# RADG-Connector-S04-V00.net
KiCad netlist of a schematic drawn in Altium Designer
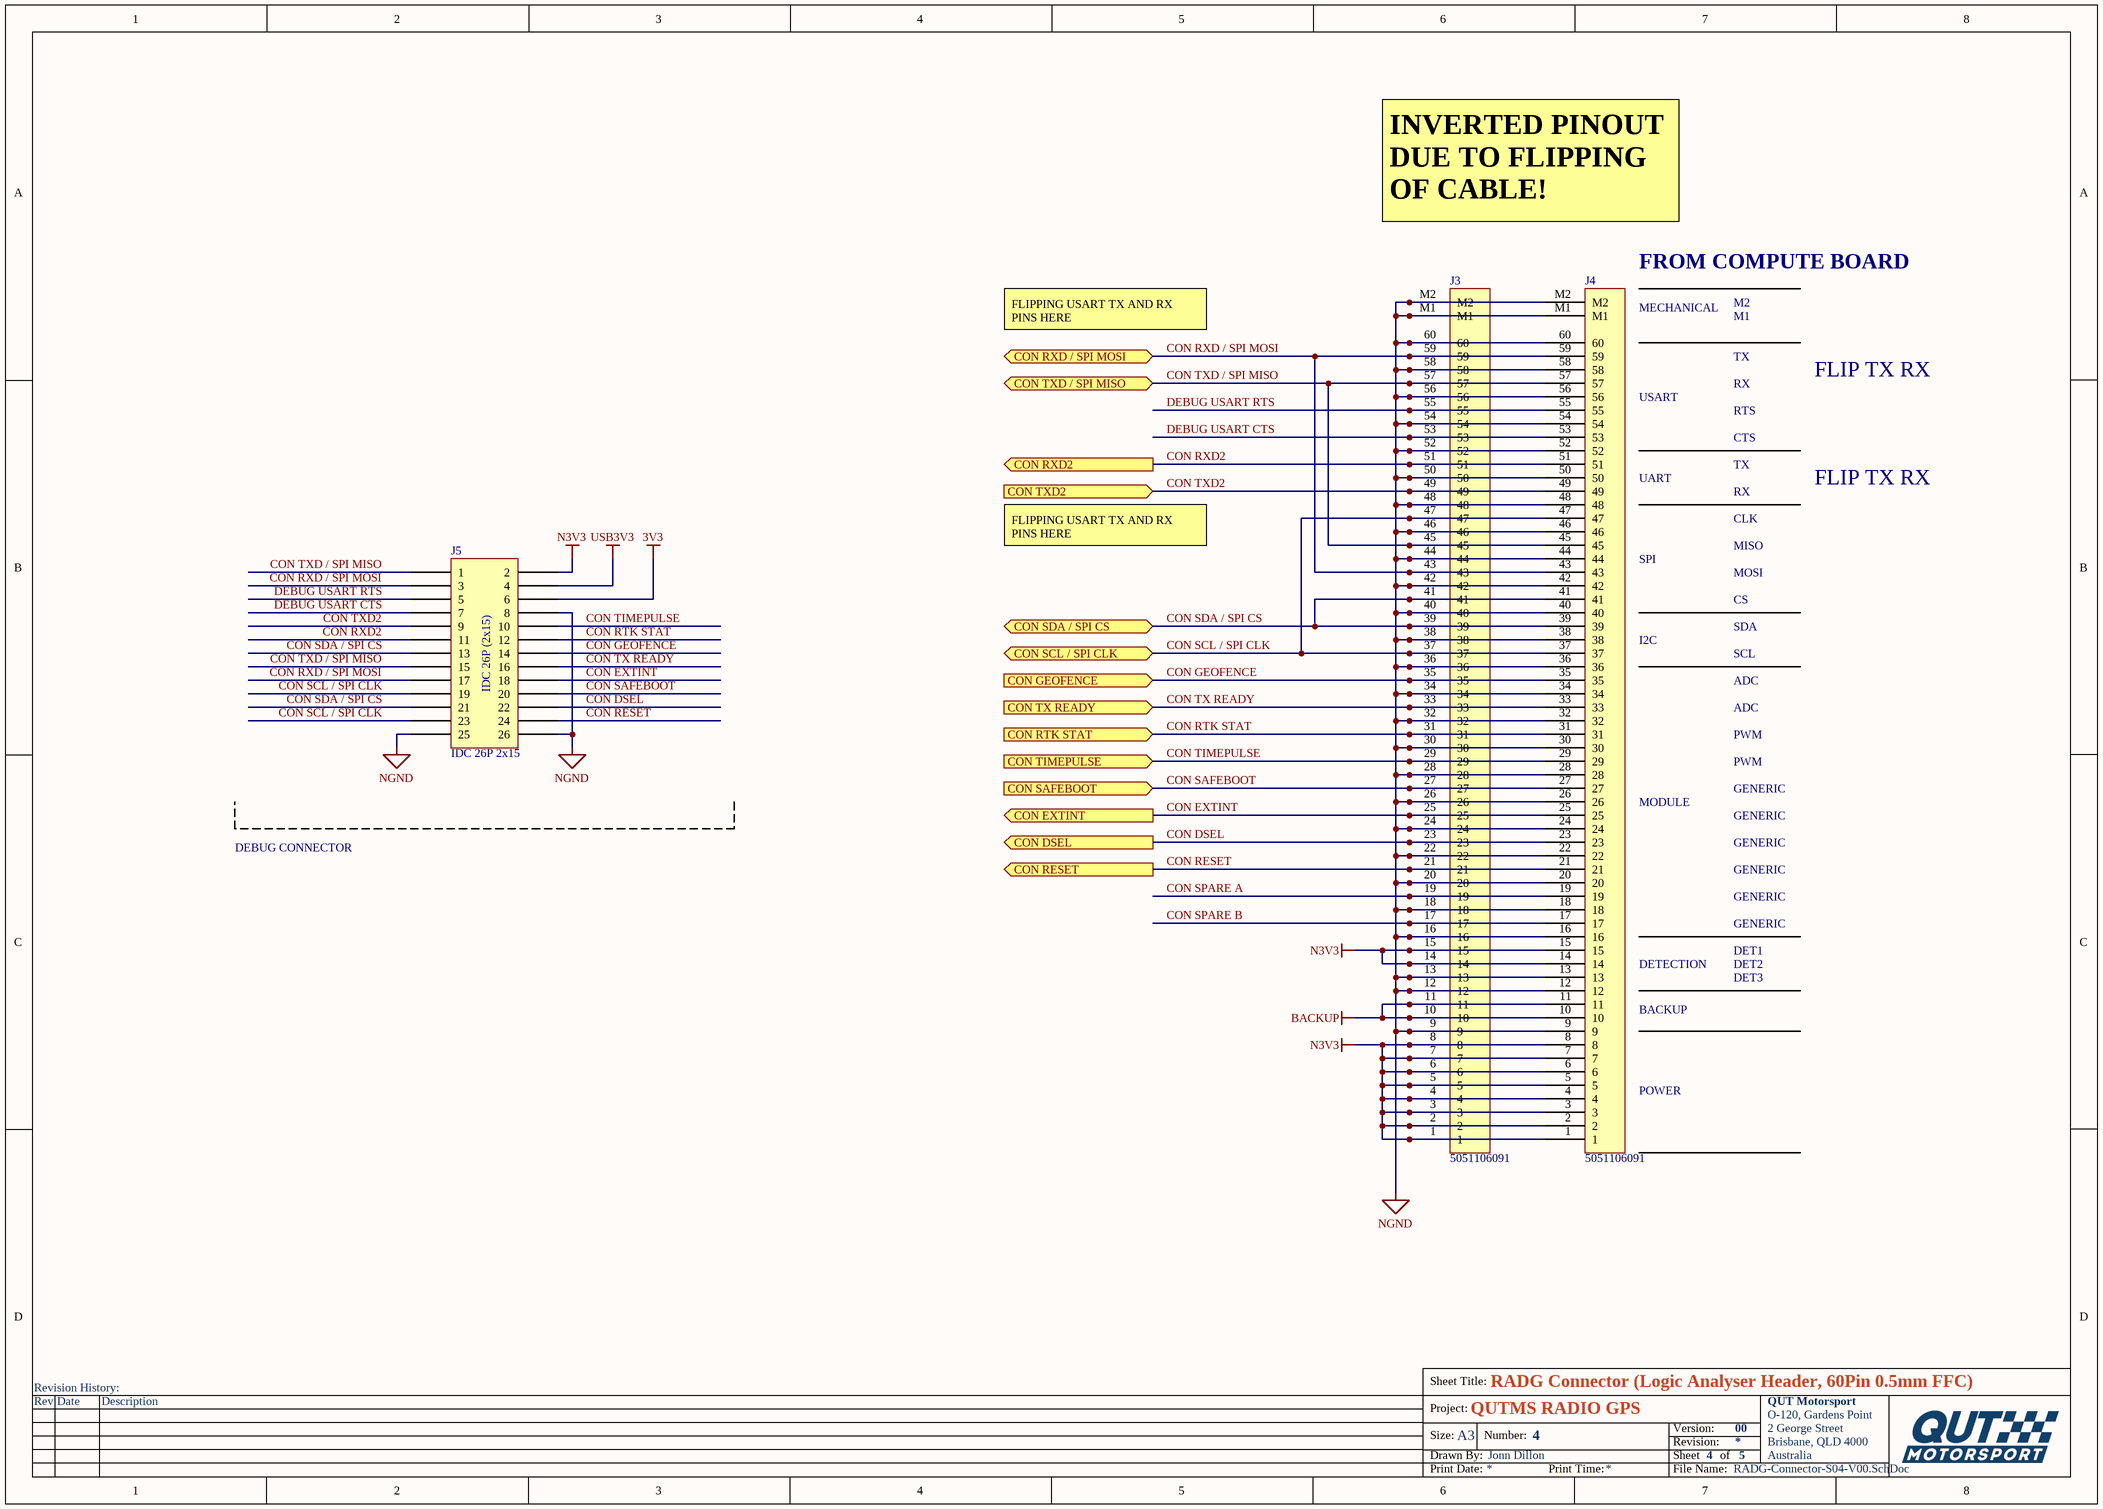
[diagram p0: RADG-Connector-S04-V00.SchDoc]

(export (version "E")
  (design (tool "Eeschema 10.0.6"))
  (components
    (comp (ref "J3")
      (value "5051106091")
      (footprint "5051106091")
      (description "60 Position FFC, FPC Connector Contacts, Bottom 0.020\" (0.50mm) Surface Mount, Right Angle")
      (libsource (lib "QUTMS_FFCConnectors") (part "5051106091"))
    )
    (comp (ref "J4")
      (value "5051106091")
      (footprint "5051106091")
      (description "60 Position FFC, FPC Connector Contacts, Bottom 0.020\" (0.50mm) Surface Mount, Right Angle")
      (libsource (lib "QUTMS_FFCConnectors") (part "5051106091"))
    )
    (comp (ref "J5")
      (value "IDC 26P 2x15")
      (footprint "IDC 2.54mm EDGE MOUNT 26p")
      (libsource (lib "QUTMS_IDCConnectors") (part "IDC 26P 2x13"))
    )
  )
  (nets
    (net (code "1") (name "/CON DSEL") (class "Default")
      (node (ref "J3") (pin "23") (pinfunction "23_23") (pintype "passive"))
      (node (ref "J4") (pin "23") (pinfunction "23_23") (pintype "passive"))
      (node (ref "J5") (pin "22") (pinfunction "22_22") (pintype "passive"))
    )
    (net (code "2") (name "/CON EXTINT") (class "Default")
      (node (ref "J3") (pin "25") (pinfunction "25_25") (pintype "passive"))
      (node (ref "J4") (pin "25") (pinfunction "25_25") (pintype "passive"))
      (node (ref "J5") (pin "18") (pinfunction "18_18") (pintype "passive"))
    )
    (net (code "3") (name "/CON GEOFENCE") (class "Default")
      (node (ref "J3") (pin "35") (pinfunction "35_35") (pintype "passive"))
      (node (ref "J4") (pin "35") (pinfunction "35_35") (pintype "passive"))
      (node (ref "J5") (pin "14") (pinfunction "14_14") (pintype "passive"))
    )
    (net (code "4") (name "/CON RESET") (class "Default")
      (node (ref "J3") (pin "21") (pinfunction "21_21") (pintype "passive"))
      (node (ref "J4") (pin "21") (pinfunction "21_21") (pintype "passive"))
      (node (ref "J5") (pin "24") (pinfunction "24_24") (pintype "passive"))
    )
    (net (code "5") (name "/CON RTK STAT") (class "Default")
      (node (ref "J3") (pin "31") (pinfunction "31_31") (pintype "passive"))
      (node (ref "J4") (pin "31") (pinfunction "31_31") (pintype "passive"))
      (node (ref "J5") (pin "12") (pinfunction "12_12") (pintype "passive"))
    )
    (net (code "6") (name "/CON RXD {slash} SPI MOSI") (class "Default")
      (node (ref "J3") (pin "43") (pinfunction "43_43") (pintype "passive"))
      (node (ref "J3") (pin "59") (pinfunction "59_59") (pintype "passive"))
      (node (ref "J4") (pin "43") (pinfunction "43_43") (pintype "passive"))
      (node (ref "J4") (pin "59") (pinfunction "59_59") (pintype "passive"))
      (node (ref "J5") (pin "17") (pinfunction "17_17") (pintype "passive"))
      (node (ref "J5") (pin "3") (pinfunction "3_3") (pintype "passive"))
    )
    (net (code "7") (name "/CON RXD2") (class "Default")
      (node (ref "J3") (pin "51") (pinfunction "51_51") (pintype "passive"))
      (node (ref "J4") (pin "51") (pinfunction "51_51") (pintype "passive"))
      (node (ref "J5") (pin "11") (pinfunction "11_11") (pintype "passive"))
    )
    (net (code "8") (name "/CON SAFEBOOT") (class "Default")
      (node (ref "J3") (pin "27") (pinfunction "27_27") (pintype "passive"))
      (node (ref "J4") (pin "27") (pinfunction "27_27") (pintype "passive"))
      (node (ref "J5") (pin "20") (pinfunction "20_20") (pintype "passive"))
    )
    (net (code "9") (name "/CON SCL {slash} SPI CLK") (class "Default")
      (node (ref "J3") (pin "37") (pinfunction "37_37") (pintype "passive"))
      (node (ref "J3") (pin "47") (pinfunction "47_47") (pintype "passive"))
      (node (ref "J4") (pin "37") (pinfunction "37_37") (pintype "passive"))
      (node (ref "J4") (pin "47") (pinfunction "47_47") (pintype "passive"))
      (node (ref "J5") (pin "19") (pinfunction "19_19") (pintype "passive"))
      (node (ref "J5") (pin "23") (pinfunction "23_23") (pintype "passive"))
    )
    (net (code "10") (name "/CON SDA {slash} SPI CS") (class "Default")
      (node (ref "J3") (pin "39") (pinfunction "39_39") (pintype "passive"))
      (node (ref "J3") (pin "41") (pinfunction "41_41") (pintype "passive"))
      (node (ref "J4") (pin "39") (pinfunction "39_39") (pintype "passive"))
      (node (ref "J4") (pin "41") (pinfunction "41_41") (pintype "passive"))
      (node (ref "J5") (pin "13") (pinfunction "13_13") (pintype "passive"))
      (node (ref "J5") (pin "21") (pinfunction "21_21") (pintype "passive"))
    )
    (net (code "11") (name "/CON SPARE A") (class "Default")
      (node (ref "J3") (pin "19") (pinfunction "19_19") (pintype "passive"))
      (node (ref "J4") (pin "19") (pinfunction "19_19") (pintype "passive"))
    )
    (net (code "12") (name "/CON SPARE B") (class "Default")
      (node (ref "J3") (pin "17") (pinfunction "17_17") (pintype "passive"))
      (node (ref "J4") (pin "17") (pinfunction "17_17") (pintype "passive"))
    )
    (net (code "13") (name "/CON TIMEPULSE") (class "Default")
      (node (ref "J3") (pin "29") (pinfunction "29_29") (pintype "passive"))
      (node (ref "J4") (pin "29") (pinfunction "29_29") (pintype "passive"))
      (node (ref "J5") (pin "10") (pinfunction "10_10") (pintype "passive"))
    )
    (net (code "14") (name "/CON TX READY") (class "Default")
      (node (ref "J3") (pin "33") (pinfunction "33_33") (pintype "passive"))
      (node (ref "J4") (pin "33") (pinfunction "33_33") (pintype "passive"))
      (node (ref "J5") (pin "16") (pinfunction "16_16") (pintype "passive"))
    )
    (net (code "15") (name "/CON TXD {slash} SPI MISO") (class "Default")
      (node (ref "J3") (pin "45") (pinfunction "45_45") (pintype "passive"))
      (node (ref "J3") (pin "57") (pinfunction "57_57") (pintype "passive"))
      (node (ref "J4") (pin "45") (pinfunction "45_45") (pintype "passive"))
      (node (ref "J4") (pin "57") (pinfunction "57_57") (pintype "passive"))
      (node (ref "J5") (pin "1") (pinfunction "1_1") (pintype "passive"))
      (node (ref "J5") (pin "15") (pinfunction "15_15") (pintype "passive"))
    )
    (net (code "16") (name "/CON TXD2") (class "Default")
      (node (ref "J3") (pin "49") (pinfunction "49_49") (pintype "passive"))
      (node (ref "J4") (pin "49") (pinfunction "49_49") (pintype "passive"))
      (node (ref "J5") (pin "9") (pinfunction "9_9") (pintype "passive"))
    )
    (net (code "17") (name "/DEBUG USART CTS") (class "Default")
      (node (ref "J3") (pin "53") (pinfunction "53_53") (pintype "passive"))
      (node (ref "J4") (pin "53") (pinfunction "53_53") (pintype "passive"))
      (node (ref "J5") (pin "7") (pinfunction "7_7") (pintype "passive"))
    )
    (net (code "18") (name "/DEBUG USART RTS") (class "Default")
      (node (ref "J3") (pin "55") (pinfunction "55_55") (pintype "passive"))
      (node (ref "J4") (pin "55") (pinfunction "55_55") (pintype "passive"))
      (node (ref "J5") (pin "5") (pinfunction "5_5") (pintype "passive"))
    )
    (net (code "19") (name "3V3") (class "Default")
      (node (ref "J5") (pin "6") (pinfunction "6_6") (pintype "passive"))
    )
    (net (code "20") (name "BACKUP") (class "Default")
      (node (ref "J3") (pin "10") (pinfunction "10_10") (pintype "passive"))
      (node (ref "J3") (pin "11") (pinfunction "11_11") (pintype "passive"))
      (node (ref "J4") (pin "10") (pinfunction "10_10") (pintype "passive"))
      (node (ref "J4") (pin "11") (pinfunction "11_11") (pintype "passive"))
    )
    (net (code "21") (name "N3V3") (class "Default")
      (node (ref "J3") (pin "1") (pinfunction "1_1") (pintype "passive"))
      (node (ref "J3") (pin "14") (pinfunction "14_14") (pintype "passive"))
      (node (ref "J3") (pin "15") (pinfunction "15_15") (pintype "passive"))
      (node (ref "J3") (pin "2") (pinfunction "2_2") (pintype "passive"))
      (node (ref "J3") (pin "3") (pinfunction "3_3") (pintype "passive"))
      (node (ref "J3") (pin "4") (pinfunction "4_4") (pintype "passive"))
      (node (ref "J3") (pin "5") (pinfunction "5_5") (pintype "passive"))
      (node (ref "J3") (pin "6") (pinfunction "6_6") (pintype "passive"))
      (node (ref "J3") (pin "7") (pinfunction "7_7") (pintype "passive"))
      (node (ref "J3") (pin "8") (pinfunction "8_8") (pintype "passive"))
      (node (ref "J4") (pin "1") (pinfunction "1_1") (pintype "passive"))
      (node (ref "J4") (pin "14") (pinfunction "14_14") (pintype "passive"))
      (node (ref "J4") (pin "15") (pinfunction "15_15") (pintype "passive"))
      (node (ref "J4") (pin "2") (pinfunction "2_2") (pintype "passive"))
      (node (ref "J4") (pin "3") (pinfunction "3_3") (pintype "passive"))
      (node (ref "J4") (pin "4") (pinfunction "4_4") (pintype "passive"))
      (node (ref "J4") (pin "5") (pinfunction "5_5") (pintype "passive"))
      (node (ref "J4") (pin "6") (pinfunction "6_6") (pintype "passive"))
      (node (ref "J4") (pin "7") (pinfunction "7_7") (pintype "passive"))
      (node (ref "J4") (pin "8") (pinfunction "8_8") (pintype "passive"))
      (node (ref "J5") (pin "2") (pinfunction "2_2") (pintype "passive"))
    )
    (net (code "22") (name "NGND") (class "Default")
      (node (ref "J3") (pin "12") (pinfunction "12_12") (pintype "passive"))
      (node (ref "J3") (pin "13") (pinfunction "13_13") (pintype "passive"))
      (node (ref "J3") (pin "16") (pinfunction "16_16") (pintype "passive"))
      (node (ref "J3") (pin "18") (pinfunction "18_18") (pintype "passive"))
      (node (ref "J3") (pin "20") (pinfunction "20_20") (pintype "passive"))
      (node (ref "J3") (pin "22") (pinfunction "22_22") (pintype "passive"))
      (node (ref "J3") (pin "24") (pinfunction "24_24") (pintype "passive"))
      (node (ref "J3") (pin "26") (pinfunction "26_26") (pintype "passive"))
      (node (ref "J3") (pin "28") (pinfunction "28_28") (pintype "passive"))
      (node (ref "J3") (pin "30") (pinfunction "30_30") (pintype "passive"))
      (node (ref "J3") (pin "32") (pinfunction "32_32") (pintype "passive"))
      (node (ref "J3") (pin "34") (pinfunction "34_34") (pintype "passive"))
      (node (ref "J3") (pin "36") (pinfunction "36_36") (pintype "passive"))
      (node (ref "J3") (pin "38") (pinfunction "38_38") (pintype "passive"))
      (node (ref "J3") (pin "40") (pinfunction "40_40") (pintype "passive"))
      (node (ref "J3") (pin "42") (pinfunction "42_42") (pintype "passive"))
      (node (ref "J3") (pin "44") (pinfunction "44_44") (pintype "passive"))
      (node (ref "J3") (pin "46") (pinfunction "46_46") (pintype "passive"))
      (node (ref "J3") (pin "48") (pinfunction "48_48") (pintype "passive"))
      (node (ref "J3") (pin "50") (pinfunction "50_50") (pintype "passive"))
      (node (ref "J3") (pin "52") (pinfunction "52_52") (pintype "passive"))
      (node (ref "J3") (pin "54") (pinfunction "54_54") (pintype "passive"))
      (node (ref "J3") (pin "56") (pinfunction "56_56") (pintype "passive"))
      (node (ref "J3") (pin "58") (pinfunction "58_58") (pintype "passive"))
      (node (ref "J3") (pin "60") (pinfunction "60_60") (pintype "passive"))
      (node (ref "J3") (pin "9") (pinfunction "9_9") (pintype "passive"))
      (node (ref "J3") (pin "M1") (pinfunction "M1_M1") (pintype "passive"))
      (node (ref "J3") (pin "M2") (pinfunction "M2_M2") (pintype "passive"))
      (node (ref "J4") (pin "12") (pinfunction "12_12") (pintype "passive"))
      (node (ref "J4") (pin "13") (pinfunction "13_13") (pintype "passive"))
      (node (ref "J4") (pin "16") (pinfunction "16_16") (pintype "passive"))
      (node (ref "J4") (pin "18") (pinfunction "18_18") (pintype "passive"))
      (node (ref "J4") (pin "20") (pinfunction "20_20") (pintype "passive"))
      (node (ref "J4") (pin "22") (pinfunction "22_22") (pintype "passive"))
      (node (ref "J4") (pin "24") (pinfunction "24_24") (pintype "passive"))
      (node (ref "J4") (pin "26") (pinfunction "26_26") (pintype "passive"))
      (node (ref "J4") (pin "28") (pinfunction "28_28") (pintype "passive"))
      (node (ref "J4") (pin "30") (pinfunction "30_30") (pintype "passive"))
      (node (ref "J4") (pin "32") (pinfunction "32_32") (pintype "passive"))
      (node (ref "J4") (pin "34") (pinfunction "34_34") (pintype "passive"))
      (node (ref "J4") (pin "36") (pinfunction "36_36") (pintype "passive"))
      (node (ref "J4") (pin "38") (pinfunction "38_38") (pintype "passive"))
      (node (ref "J4") (pin "40") (pinfunction "40_40") (pintype "passive"))
      (node (ref "J4") (pin "42") (pinfunction "42_42") (pintype "passive"))
      (node (ref "J4") (pin "44") (pinfunction "44_44") (pintype "passive"))
      (node (ref "J4") (pin "46") (pinfunction "46_46") (pintype "passive"))
      (node (ref "J4") (pin "48") (pinfunction "48_48") (pintype "passive"))
      (node (ref "J4") (pin "50") (pinfunction "50_50") (pintype "passive"))
      (node (ref "J4") (pin "52") (pinfunction "52_52") (pintype "passive"))
      (node (ref "J4") (pin "54") (pinfunction "54_54") (pintype "passive"))
      (node (ref "J4") (pin "56") (pinfunction "56_56") (pintype "passive"))
      (node (ref "J4") (pin "58") (pinfunction "58_58") (pintype "passive"))
      (node (ref "J4") (pin "60") (pinfunction "60_60") (pintype "passive"))
      (node (ref "J4") (pin "9") (pinfunction "9_9") (pintype "passive"))
      (node (ref "J4") (pin "M1") (pinfunction "M1_M1") (pintype "passive"))
      (node (ref "J4") (pin "M2") (pinfunction "M2_M2") (pintype "passive"))
      (node (ref "J5") (pin "25") (pinfunction "25_25") (pintype "passive"))
      (node (ref "J5") (pin "26") (pinfunction "26_26") (pintype "passive"))
      (node (ref "J5") (pin "8") (pinfunction "8_8") (pintype "passive"))
    )
    (net (code "23") (name "USB3V3") (class "Default")
      (node (ref "J5") (pin "4") (pinfunction "4_4") (pintype "passive"))
    )
  )
)
